# meltdown_protection.net
KiCad netlist of a schematic drawn in Altium Designer
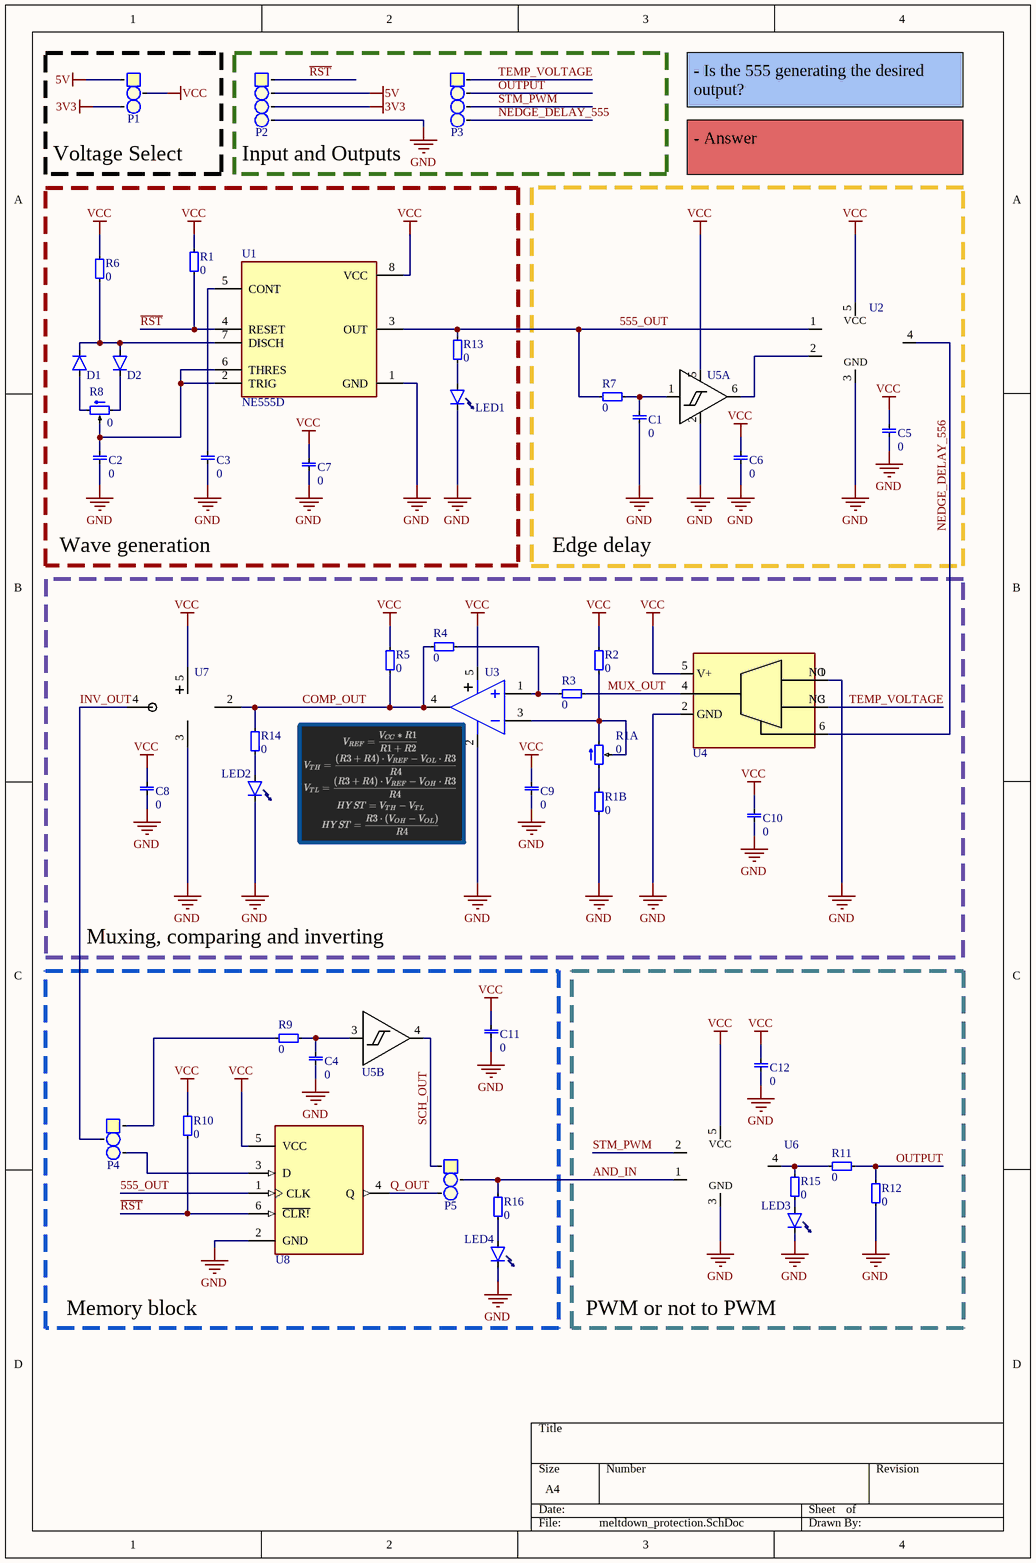
[diagram p0: meltdown_protection.SchDoc]

(export (version "E")
  (design (tool "Eeschema 10.0.6"))
  (components
    (comp (ref "C1")
      (value "0")
      (footprint "0603 cap")
      (fields (field (name "Comment") "0603, capacitor"))
      (libsource (lib "jclib") (part "0603, capacitor"))
    )
    (comp (ref "C2")
      (value "0")
      (footprint "0603 cap")
      (fields (field (name "Comment") "0603, capacitor"))
      (libsource (lib "jclib") (part "0603, capacitor"))
    )
    (comp (ref "C3")
      (value "0")
      (footprint "0603 cap")
      (fields (field (name "Comment") "0603, capacitor"))
      (libsource (lib "jclib") (part "0603, capacitor"))
    )
    (comp (ref "C4")
      (value "0")
      (footprint "0603 cap")
      (fields (field (name "Comment") "0603, capacitor"))
      (libsource (lib "jclib") (part "0603, capacitor"))
    )
    (comp (ref "C5")
      (value "0")
      (footprint "0603 cap")
      (fields (field (name "Comment") "0603, capacitor"))
      (libsource (lib "jclib") (part "0603, capacitor"))
    )
    (comp (ref "C6")
      (value "0")
      (footprint "0603 cap")
      (fields (field (name "Comment") "0603, capacitor"))
      (libsource (lib "jclib") (part "0603, capacitor"))
    )
    (comp (ref "C7")
      (value "0")
      (footprint "0603 cap")
      (fields (field (name "Comment") "0603, capacitor"))
      (libsource (lib "jclib") (part "0603, capacitor"))
    )
    (comp (ref "C8")
      (value "0")
      (footprint "0603 cap")
      (fields (field (name "Comment") "0603, capacitor"))
      (libsource (lib "jclib") (part "0603, capacitor"))
    )
    (comp (ref "C9")
      (value "0")
      (footprint "0603 cap")
      (fields (field (name "Comment") "0603, capacitor"))
      (libsource (lib "jclib") (part "0603, capacitor"))
    )
    (comp (ref "C10")
      (value "0")
      (footprint "0603 cap")
      (fields (field (name "Comment") "0603, capacitor"))
      (libsource (lib "jclib") (part "0603, capacitor"))
    )
    (comp (ref "C11")
      (value "0")
      (footprint "0603 cap")
      (fields (field (name "Comment") "0603, capacitor"))
      (libsource (lib "jclib") (part "0603, capacitor"))
    )
    (comp (ref "C12")
      (value "0")
      (footprint "0603 cap")
      (fields (field (name "Comment") "0603, capacitor"))
      (libsource (lib "jclib") (part "0603, capacitor"))
    )
    (comp (ref "D1") (value "Diode, SMD") (footprint "SOD323") (libsource (lib "jclib") (part "Diode, SMD")))
    (comp (ref "D2") (value "Diode, SMD") (footprint "SOD323") (libsource (lib "jclib") (part "Diode, SMD")))
    (comp (ref "LED1")
      (value "0805, LED")
      (footprint "0805_led")
      (libsource (lib "jclib") (part "0805, LED"))
    )
    (comp (ref "LED2")
      (value "0805, LED")
      (footprint "0805_led")
      (libsource (lib "jclib") (part "0805, LED"))
    )
    (comp (ref "LED3")
      (value "0805, LED")
      (footprint "0805_led")
      (libsource (lib "jclib") (part "0805, LED"))
    )
    (comp (ref "LED4")
      (value "0805, LED")
      (footprint "0805_led")
      (libsource (lib "jclib") (part "0805, LED"))
    )
    (comp (ref "P1")
      (value "1x3 Pin Header Mux")
      (footprint "padThree_L")
      (description "2.54 mm")
      (libsource (lib "jclib") (part "1x3 Pin Header Mux"))
    )
    (comp (ref "P2")
      (value "4x1 Pin Header")
      (footprint "padFour_L")
      (description "2.54 mm")
      (libsource (lib "jclib") (part "1x4 Pin Header"))
    )
    (comp (ref "P3")
      (value "4x1 Pin Header")
      (footprint "padFour_L")
      (description "2.54 mm")
      (libsource (lib "jclib") (part "1x4 Pin Header"))
    )
    (comp (ref "P4")
      (value "1x3 Pin Header Mux")
      (footprint "padThree_L")
      (description "2.54 mm")
      (libsource (lib "") (part "1x3 Pin Header Mux_1"))
    )
    (comp (ref "P5")
      (value "1x3 Pin Header Mux")
      (footprint "padThree_L")
      (description "2.54 mm")
      (libsource (lib "jclib") (part "1x3 Pin Header Mux"))
    )
    (comp (ref "R1")
      (value "0")
      (footprint "0603")
      (fields (field (name "Comment") "0603, resistor"))
      (libsource (lib "jclib") (part "0603, resistor"))
    )
    (comp (ref "R1A")
      (value "0")
      (footprint "PV36W104C01B00")
      (fields (field (name "Comment") "Pot"))
      (libsource (lib "jclib") (part "Pot"))
    )
    (comp (ref "R1B")
      (value "0")
      (footprint "0603")
      (fields (field (name "Comment") "0603, resistor"))
      (libsource (lib "jclib") (part "0603, resistor"))
    )
    (comp (ref "R2")
      (value "0")
      (footprint "0603")
      (fields (field (name "Comment") "0603, resistor"))
      (libsource (lib "jclib") (part "0603, resistor"))
    )
    (comp (ref "R3")
      (value "0")
      (footprint "0603")
      (fields (field (name "Comment") "0603, resistor"))
      (libsource (lib "jclib") (part "0603, resistor"))
    )
    (comp (ref "R4")
      (value "0")
      (footprint "0603")
      (fields (field (name "Comment") "0603, resistor"))
      (libsource (lib "jclib") (part "0603, resistor"))
    )
    (comp (ref "R5")
      (value "0")
      (footprint "0603")
      (fields (field (name "Comment") "0603, resistor"))
      (libsource (lib "jclib") (part "0603, resistor"))
    )
    (comp (ref "R6")
      (value "0")
      (footprint "0603")
      (fields (field (name "Comment") "0603, resistor"))
      (libsource (lib "jclib") (part "0603, resistor"))
    )
    (comp (ref "R7")
      (value "0")
      (footprint "0603")
      (fields (field (name "Comment") "0603, resistor"))
      (libsource (lib "jclib") (part "0603, resistor"))
    )
    (comp (ref "R8")
      (value "0")
      (footprint "PV36W104C01B00")
      (fields (field (name "Comment") "Pot"))
      (libsource (lib "jclib") (part "Pot"))
    )
    (comp (ref "R9")
      (value "0")
      (footprint "0603")
      (fields (field (name "Comment") "0603, resistor"))
      (libsource (lib "jclib") (part "0603, resistor"))
    )
    (comp (ref "R10")
      (value "0")
      (footprint "0603")
      (fields (field (name "Comment") "0603, resistor"))
      (libsource (lib "jclib") (part "0603, resistor"))
    )
    (comp (ref "R11")
      (value "0")
      (footprint "0603")
      (fields (field (name "Comment") "0603, resistor"))
      (libsource (lib "jclib") (part "0603, resistor"))
    )
    (comp (ref "R12")
      (value "0")
      (footprint "0603")
      (fields (field (name "Comment") "0603, resistor"))
      (libsource (lib "jclib") (part "0603, resistor"))
    )
    (comp (ref "R13")
      (value "0")
      (footprint "0603")
      (fields (field (name "Comment") "0603, resistor"))
      (libsource (lib "jclib") (part "0603, resistor"))
    )
    (comp (ref "R14")
      (value "0")
      (footprint "0603")
      (fields (field (name "Comment") "0603, resistor"))
      (libsource (lib "jclib") (part "0603, resistor"))
    )
    (comp (ref "R15")
      (value "0")
      (footprint "0603")
      (fields (field (name "Comment") "0603, resistor"))
      (libsource (lib "jclib") (part "0603, resistor"))
    )
    (comp (ref "R16")
      (value "0")
      (footprint "0603")
      (fields (field (name "Comment") "0603, resistor"))
      (libsource (lib "jclib") (part "0603, resistor"))
    )
    (comp (ref "U1") (value "NE555D") (footprint "SOIC8") (libsource (lib "jclib") (part "NE555D")))
    (comp (ref "U2")
      (value "SN74LVC1G32DBVT")
      (footprint "SOT23-5")
      (description "Single 2-input, 1.65-V to 5.5-V OR gate")
      (fields (field (name "MF") "Texas Instruments"))
      (libsource (lib "jclib") (part "SN74LVC1G32DBVT"))
    )
    (comp (ref "U3")
      (value "MCP6V66UT-E/LTY")
      (footprint "SC70P210X110-5N")
      (description "Linear High Precision Op Amps-Chopper Stabilized, 1000kHz, 1.8Vto5.5V, SC70-5, RoHS")
      (fields (field (name "MANUFACTURER") "Microchip"))
      (libsource (lib "jclib") (part "MCP6V66UT-E/LTY"))
    )
    (comp (ref "U4")
      (value "TS5A3159DCKR")
      (footprint "SOT65P210X110-6N")
      (description "1-?, 5-V, 2:1 (SPDT), 1-channel analog switch 6-SC70 -40 to 85")
      (fields (field (name "MF") "Texas Instruments"))
      (libsource (lib "jclib") (part "TS5A3159DCKR"))
    )
    (comp (ref "U5")
      (value "SN74LVC2G17DBVT")
      (footprint "jclib:SOT95P280X145-6N")
      (description "Dual Schmitt-Trigger Buffer")
      (fields (field (name "MF") "Texas Instruments"))
      (libsource (lib "jclib") (part "SN74LVC2G17DBVT"))
    )
    (comp (ref "U6")
      (value "SN74LVC1G08DBVR")
      (footprint "SOT95P280X145-5N")
      (description "Single 2-Input Positive-AND Gate 5-SOT-23 -40 to 125")
      (fields (field (name "MF") "Texas Instruments"))
      (libsource (lib "jclib") (part "SN74LVC1G08DBVR"))
    )
    (comp (ref "U7")
      (value "SN74LVC1G04DBVR")
      (footprint "SOT95P280X145-5N")
      (description "Single Inverter 5-SOT-23 -40 to 125")
      (libsource (lib "jclib") (part "SN74LVC1G04DBVR"))
    )
    (comp (ref "U8")
      (value "SN74LVC1G175DBVR")
      (footprint "SOT95P280X145-6N")
      (description "Single D-Type Flip-Flop with Asynchronous Clear 6-SOT-23 -40 to 125")
      (fields (field (name "MF") "Texas Instruments") (field (name "DIGI-KEY_PART_NUMBER") "296-17617-1-ND"))
      (libsource (lib "jclib") (part "SN74LVC1G175DBVR"))
    )
  )
  (nets
    (net (code "1") (name "/555_OUT") (class "Default")
      (node (ref "R13") (pin "0") (pinfunction "0_0") (pintype "passive"))
      (node (ref "R7") (pin "1") (pinfunction "1_1") (pintype "passive"))
      (node (ref "U1") (pin "3") (pinfunction "OUT_3") (pintype "passive"))
      (node (ref "U2") (pin "1") (pinfunction "A_1") (pintype "passive"))
      (node (ref "U8") (pin "1") (pinfunction "CLK_1") (pintype "input"))
    )
    (net (code "2") (name "/AND_IN") (class "Default")
      (node (ref "P5") (pin "2") (pinfunction "2_2") (pintype "passive"))
      (node (ref "R16") (pin "0") (pinfunction "0_0") (pintype "passive"))
      (node (ref "U6") (pin "1") (pinfunction "A_1") (pintype "passive"))
    )
    (net (code "3") (name "/COMP_OUT") (class "Default")
      (node (ref "R14") (pin "0") (pinfunction "0_0") (pintype "passive"))
      (node (ref "R4") (pin "1") (pinfunction "1_1") (pintype "passive"))
      (node (ref "R5") (pin "0") (pinfunction "0_0") (pintype "passive"))
      (node (ref "U3") (pin "4") (pinfunction "OUT_4") (pintype "passive"))
      (node (ref "U7") (pin "2") (pinfunction "A_2") (pintype "passive"))
    )
    (net (code "4") (name "/INV_OUT") (class "Default")
      (node (ref "P4") (pin "2") (pinfunction "2_2") (pintype "passive"))
      (node (ref "U7") (pin "4") (pinfunction "Y_4") (pintype "passive"))
    )
    (net (code "5") (name "/MUX_OUT") (class "Default")
      (node (ref "R3") (pin "0") (pinfunction "0_0") (pintype "passive"))
      (node (ref "U4") (pin "4") (pinfunction "COM_4") (pintype "passive"))
    )
    (net (code "6") (name "/NEDGE_DELAY_555") (class "Default")
      (node (ref "P3") (pin "4") (pinfunction "4_4") (pintype "passive"))
    )
    (net (code "7") (name "/NEDGE_DELAY_556") (class "Default")
      (node (ref "U2") (pin "4") (pinfunction "Y_4") (pintype "passive"))
      (node (ref "U4") (pin "6") (pinfunction "IN_6") (pintype "passive"))
    )
    (net (code "8") (name "/OUTPUT") (class "Default")
      (node (ref "P3") (pin "2") (pinfunction "2_2") (pintype "passive"))
      (node (ref "R11") (pin "0") (pinfunction "0_0") (pintype "passive"))
      (node (ref "R12") (pin "0") (pinfunction "0_0") (pintype "passive"))
    )
    (net (code "9") (name "/Q_OUT") (class "Default")
      (node (ref "P5") (pin "3") (pinfunction "3_3") (pintype "passive"))
      (node (ref "U8") (pin "4") (pinfunction "Q_4") (pintype "output"))
    )
    (net (code "10") (name "/SCH_OUT") (class "Default")
      (node (ref "P5") (pin "1") (pinfunction "1_1") (pintype "passive"))
      (node (ref "U5") (pin "4") (pinfunction "2Y_4") (pintype "passive"))
    )
    (net (code "11") (name "/STM_PWM") (class "Default")
      (node (ref "P3") (pin "3") (pinfunction "3_3") (pintype "passive"))
      (node (ref "U6") (pin "2") (pinfunction "B_2") (pintype "passive"))
    )
    (net (code "12") (name "/TEMP_VOLTAGE") (class "Default")
      (node (ref "P3") (pin "1") (pinfunction "1_1") (pintype "passive"))
      (node (ref "U4") (pin "3") (pinfunction "NC_3") (pintype "passive"))
    )
    (net (code "13") (name "/~{RST}") (class "Default")
      (node (ref "P2") (pin "1") (pinfunction "1_1") (pintype "passive"))
      (node (ref "R1") (pin "1") (pinfunction "1_1") (pintype "passive"))
      (node (ref "R10") (pin "0") (pinfunction "0_0") (pintype "passive"))
      (node (ref "U1") (pin "4") (pinfunction "RESET_4") (pintype "passive"))
      (node (ref "U8") (pin "6") (pinfunction "~{CLR!}_6") (pintype "input"))
    )
    (net (code "14") (name "3V3") (class "Default")
      (node (ref "P1") (pin "3") (pinfunction "3_3") (pintype "passive"))
      (node (ref "P2") (pin "3") (pinfunction "3_3") (pintype "passive"))
    )
    (net (code "15") (name "5V") (class "Default")
      (node (ref "P1") (pin "1") (pinfunction "1_1") (pintype "passive"))
      (node (ref "P2") (pin "2") (pinfunction "2_2") (pintype "passive"))
    )
    (net (code "16") (name "GND") (class "Default")
      (node (ref "C1") (pin "0") (pinfunction "0_0") (pintype "passive"))
      (node (ref "C10") (pin "0") (pinfunction "0_0") (pintype "passive"))
      (node (ref "C11") (pin "0") (pinfunction "0_0") (pintype "passive"))
      (node (ref "C12") (pin "0") (pinfunction "0_0") (pintype "passive"))
      (node (ref "C2") (pin "0") (pinfunction "0_0") (pintype "passive"))
      (node (ref "C3") (pin "0") (pinfunction "0_0") (pintype "passive"))
      (node (ref "C4") (pin "0") (pinfunction "0_0") (pintype "passive"))
      (node (ref "C5") (pin "0") (pinfunction "0_0") (pintype "passive"))
      (node (ref "C6") (pin "0") (pinfunction "0_0") (pintype "passive"))
      (node (ref "C7") (pin "0") (pinfunction "0_0") (pintype "passive"))
      (node (ref "C8") (pin "0") (pinfunction "0_0") (pintype "passive"))
      (node (ref "C9") (pin "0") (pinfunction "0_0") (pintype "passive"))
      (node (ref "LED1") (pin "0") (pinfunction "Cathode_0") (pintype "passive"))
      (node (ref "LED2") (pin "0") (pinfunction "Cathode_0") (pintype "passive"))
      (node (ref "LED3") (pin "0") (pinfunction "Cathode_0") (pintype "passive"))
      (node (ref "LED4") (pin "0") (pinfunction "Cathode_0") (pintype "passive"))
      (node (ref "P2") (pin "4") (pinfunction "4_4") (pintype "passive"))
      (node (ref "R12") (pin "1") (pinfunction "1_1") (pintype "passive"))
      (node (ref "R1B") (pin "1") (pinfunction "1_1") (pintype "passive"))
      (node (ref "U1") (pin "1") (pinfunction "GND_1") (pintype "power_in"))
      (node (ref "U2") (pin "3") (pinfunction "GND_3") (pintype "power_in"))
      (node (ref "U3") (pin "2") (pinfunction "V-_2") (pintype "passive"))
      (node (ref "U4") (pin "1") (pinfunction "NO_1") (pintype "passive"))
      (node (ref "U4") (pin "2") (pinfunction "GND_2") (pintype "power_in"))
      (node (ref "U5") (pin "2") (pinfunction "GND_2") (pintype "power_in"))
      (node (ref "U6") (pin "3") (pinfunction "GND_3") (pintype "power_in"))
      (node (ref "U7") (pin "3") (pinfunction "GND_3") (pintype "power_in"))
      (node (ref "U8") (pin "2") (pinfunction "GND_2") (pintype "power_in"))
    )
    (net (code "17") (name "Net-(D1-Pad2)") (class "Default")
      (node (ref "D1") (pin "2") (pinfunction "2_2") (pintype "passive"))
      (node (ref "R8") (pin "3") (pinfunction "3_3") (pintype "passive"))
    )
    (net (code "18") (name "Net-(D2-Pad1)") (class "Default")
      (node (ref "D2") (pin "1") (pinfunction "1_1") (pintype "passive"))
      (node (ref "R8") (pin "1") (pinfunction "1_1") (pintype "passive"))
    )
    (net (code "19") (name "Net-(LED1-Pad1)") (class "Default")
      (node (ref "LED1") (pin "1") (pinfunction "1_1") (pintype "passive"))
      (node (ref "R13") (pin "1") (pinfunction "1_1") (pintype "passive"))
    )
    (net (code "20") (name "Net-(LED2-Pad1)") (class "Default")
      (node (ref "LED2") (pin "1") (pinfunction "1_1") (pintype "passive"))
      (node (ref "R14") (pin "1") (pinfunction "1_1") (pintype "passive"))
    )
    (net (code "21") (name "Net-(LED3-Pad1)") (class "Default")
      (node (ref "LED3") (pin "1") (pinfunction "1_1") (pintype "passive"))
      (node (ref "R15") (pin "1") (pinfunction "1_1") (pintype "passive"))
    )
    (net (code "22") (name "Net-(LED4-Pad1)") (class "Default")
      (node (ref "LED4") (pin "1") (pinfunction "1_1") (pintype "passive"))
      (node (ref "R16") (pin "1") (pinfunction "1_1") (pintype "passive"))
    )
    (net (code "23") (name "Net-(P4-Pad1)") (class "Default")
      (node (ref "P4") (pin "1") (pinfunction "1_1") (pintype "passive"))
      (node (ref "R9") (pin "1") (pinfunction "1_1") (pintype "passive"))
    )
    (net (code "24") (name "Net-(R1A-Pad1)") (class "Default")
      (node (ref "R1A") (pin "1") (pinfunction "1_1") (pintype "passive"))
      (node (ref "R1B") (pin "0") (pinfunction "0_0") (pintype "passive"))
    )
    (net (code "25") (name "Net-(U1-CONT)") (class "Default")
      (node (ref "C3") (pin "1") (pinfunction "1_1") (pintype "passive"))
      (node (ref "U1") (pin "5") (pinfunction "CONT_5") (pintype "passive"))
    )
    (net (code "26") (name "Net-(U1-DISCH)") (class "Default")
      (node (ref "D1") (pin "1") (pinfunction "1_1") (pintype "passive"))
      (node (ref "D2") (pin "2") (pinfunction "2_2") (pintype "passive"))
      (node (ref "R6") (pin "1") (pinfunction "1_1") (pintype "passive"))
      (node (ref "U1") (pin "7") (pinfunction "DISCH_7") (pintype "passive"))
    )
    (net (code "27") (name "Net-(U1-THRES)") (class "Default")
      (node (ref "C2") (pin "1") (pinfunction "1_1") (pintype "passive"))
      (node (ref "R8") (pin "2") (pinfunction "2_2") (pintype "passive"))
      (node (ref "U1") (pin "2") (pinfunction "TRIG_2") (pintype "passive"))
      (node (ref "U1") (pin "6") (pinfunction "THRES_6") (pintype "passive"))
    )
    (net (code "28") (name "Net-(U2-B)") (class "Default")
      (node (ref "U2") (pin "2") (pinfunction "B_2") (pintype "passive"))
      (node (ref "U5") (pin "6") (pinfunction "1Y_6") (pintype "passive"))
    )
    (net (code "29") (name "Net-(U3-IN+)") (class "Default")
      (node (ref "R3") (pin "1") (pinfunction "1_1") (pintype "passive"))
      (node (ref "R4") (pin "0") (pinfunction "0_0") (pintype "passive"))
      (node (ref "U3") (pin "1") (pinfunction "IN+_1") (pintype "passive"))
    )
    (net (code "30") (name "Net-(U3-IN-)") (class "Default")
      (node (ref "R1A") (pin "2") (pinfunction "2_2") (pintype "passive"))
      (node (ref "R1A") (pin "3") (pinfunction "3_3") (pintype "passive"))
      (node (ref "R2") (pin "1") (pinfunction "1_1") (pintype "passive"))
      (node (ref "U3") (pin "3") (pinfunction "IN-_3") (pintype "passive"))
    )
    (net (code "31") (name "Net-(U5A-1A)") (class "Default")
      (node (ref "C1") (pin "1") (pinfunction "1_1") (pintype "passive"))
      (node (ref "R7") (pin "0") (pinfunction "0_0") (pintype "passive"))
      (node (ref "U5") (pin "1") (pinfunction "1A_1") (pintype "passive"))
    )
    (net (code "32") (name "Net-(U5B-2A)") (class "Default")
      (node (ref "C4") (pin "1") (pinfunction "1_1") (pintype "passive"))
      (node (ref "R9") (pin "0") (pinfunction "0_0") (pintype "passive"))
      (node (ref "U5") (pin "3") (pinfunction "2A_3") (pintype "passive"))
    )
    (net (code "33") (name "Net-(U6-Y)") (class "Default")
      (node (ref "R11") (pin "1") (pinfunction "1_1") (pintype "passive"))
      (node (ref "R15") (pin "0") (pinfunction "0_0") (pintype "passive"))
      (node (ref "U6") (pin "4") (pinfunction "Y_4") (pintype "passive"))
    )
    (net (code "34") (name "Net-(U8-D)") (class "Default")
      (node (ref "P4") (pin "3") (pinfunction "3_3") (pintype "passive"))
      (node (ref "U8") (pin "3") (pinfunction "D_3") (pintype "input"))
    )
    (net (code "35") (name "VCC") (class "Default")
      (node (ref "C10") (pin "1") (pinfunction "1_1") (pintype "passive"))
      (node (ref "C11") (pin "1") (pinfunction "1_1") (pintype "passive"))
      (node (ref "C12") (pin "1") (pinfunction "1_1") (pintype "passive"))
      (node (ref "C5") (pin "1") (pinfunction "1_1") (pintype "passive"))
      (node (ref "C6") (pin "1") (pinfunction "1_1") (pintype "passive"))
      (node (ref "C7") (pin "1") (pinfunction "1_1") (pintype "passive"))
      (node (ref "C8") (pin "1") (pinfunction "1_1") (pintype "passive"))
      (node (ref "C9") (pin "1") (pinfunction "1_1") (pintype "passive"))
      (node (ref "P1") (pin "2") (pinfunction "2_2") (pintype "passive"))
      (node (ref "R1") (pin "0") (pinfunction "0_0") (pintype "passive"))
      (node (ref "R10") (pin "1") (pinfunction "1_1") (pintype "passive"))
      (node (ref "R2") (pin "0") (pinfunction "0_0") (pintype "passive"))
      (node (ref "R5") (pin "1") (pinfunction "1_1") (pintype "passive"))
      (node (ref "R6") (pin "0") (pinfunction "0_0") (pintype "passive"))
      (node (ref "U1") (pin "8") (pinfunction "VCC_8") (pintype "power_in"))
      (node (ref "U2") (pin "5") (pinfunction "VCC_5") (pintype "power_in"))
      (node (ref "U3") (pin "5") (pinfunction "V+_5") (pintype "passive"))
      (node (ref "U4") (pin "5") (pinfunction "V+_5") (pintype "power_in"))
      (node (ref "U5") (pin "5") (pinfunction "VCC_5") (pintype "power_in"))
      (node (ref "U6") (pin "5") (pinfunction "VCC_5") (pintype "power_in"))
      (node (ref "U7") (pin "5") (pinfunction "VCC_5") (pintype "power_in"))
      (node (ref "U8") (pin "5") (pinfunction "VCC_5") (pintype "power_in"))
    )
  )
)
